# 8266_DIYIOT_Board_H_G_B_R_GND.net
KiCad netlist of a schematic drawn in EAGLE
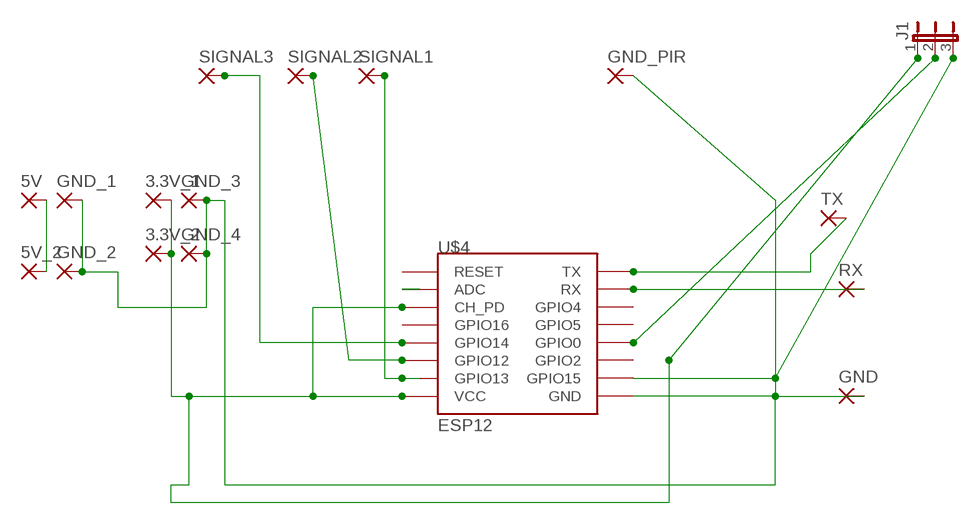
[diagram p0: schematic, sheet 1]

(export (version "E")
  (design (tool "Eeschema 10.0.6"))
  (components
    (comp (ref "3.3V_1")
      (value "2,15/1,0")
      (footprint "eagle-import:2,15_1,0")
      (libsource (lib "eagle-import") (part "2,15/1,0"))
    )
    (comp (ref "3.3V_2")
      (value "2,15/1,0")
      (footprint "eagle-import:2,15_1,0")
      (libsource (lib "eagle-import") (part "2,15/1,0"))
    )
    (comp (ref "5V")
      (value "2,15/1,0")
      (footprint "eagle-import:2,15_1,0")
      (libsource (lib "eagle-import") (part "2,15/1,0"))
    )
    (comp (ref "5V_2")
      (value "2,15/1,0")
      (footprint "eagle-import:2,15_1,0")
      (libsource (lib "eagle-import") (part "2,15/1,0"))
    )
    (comp (ref "GND")
      (value "2,15/1,0")
      (footprint "eagle-import:2,15_1,0")
      (libsource (lib "eagle-import") (part "2,15/1,0"))
    )
    (comp (ref "GND_1")
      (value "2,15/1,0")
      (footprint "eagle-import:2,15_1,0")
      (libsource (lib "eagle-import") (part "2,15/1,0"))
    )
    (comp (ref "GND_2")
      (value "2,15/1,0")
      (footprint "eagle-import:2,15_1,0")
      (libsource (lib "eagle-import") (part "2,15/1,0"))
    )
    (comp (ref "GND_3")
      (value "2,15/1,0")
      (footprint "eagle-import:2,15_1,0")
      (libsource (lib "eagle-import") (part "2,15/1,0"))
    )
    (comp (ref "GND_4")
      (value "2,15/1,0")
      (footprint "eagle-import:2,15_1,0")
      (libsource (lib "eagle-import") (part "2,15/1,0"))
    )
    (comp (ref "GND_PIR")
      (value "2,15/1,0")
      (footprint "eagle-import:2,15_1,0")
      (libsource (lib "eagle-import") (part "2,15/1,0"))
    )
    (comp (ref "J1")
      (value "JP2E")
      (footprint "eagle-import:JP2")
      (libsource (lib "eagle-import") (part "JP2E"))
    )
    (comp (ref "RX")
      (value "2,15/1,0")
      (footprint "eagle-import:2,15_1,0")
      (libsource (lib "eagle-import") (part "2,15/1,0"))
    )
    (comp (ref "SIGNAL1")
      (value "2,15/1,0")
      (footprint "eagle-import:2,15_1,0")
      (libsource (lib "eagle-import") (part "2,15/1,0"))
    )
    (comp (ref "SIGNAL2")
      (value "2,15/1,0")
      (footprint "eagle-import:2,15_1,0")
      (libsource (lib "eagle-import") (part "2,15/1,0"))
    )
    (comp (ref "SIGNAL3")
      (value "2,15/1,0")
      (footprint "eagle-import:2,15_1,0")
      (libsource (lib "eagle-import") (part "2,15/1,0"))
    )
    (comp (ref "TX")
      (value "2,15/1,0")
      (footprint "eagle-import:2,15_1,0")
      (libsource (lib "eagle-import") (part "2,15/1,0"))
    )
    (comp (ref "U$4")
      (value "ESP12")
      (footprint "eagle-import:ESP12")
      (libsource (lib "eagle-import") (part "ESP12"))
    )
  )
  (nets
    (net (code "1") (name "/5V") (class "Default")
      (node (ref "5V") (pin "1") (pinfunction "P_1") (pintype "passive"))
      (node (ref "5V_2") (pin "1") (pinfunction "P_1") (pintype "passive"))
      (node (ref "GND") (pin "1") (pinfunction "P_1") (pintype "passive"))
      (node (ref "GND_1") (pin "1") (pinfunction "P_1") (pintype "passive"))
      (node (ref "GND_2") (pin "1") (pinfunction "P_1") (pintype "passive"))
      (node (ref "GND_3") (pin "1") (pinfunction "P_1") (pintype "passive"))
      (node (ref "GND_4") (pin "1") (pinfunction "P_1") (pintype "passive"))
      (node (ref "GND_PIR") (pin "1") (pinfunction "P_1") (pintype "passive"))
      (node (ref "J1") (pin "3") (pinfunction "3_3") (pintype "passive"))
      (node (ref "U$4") (pin "GND") (pinfunction "GND_GND") (pintype "bidirectional"))
      (node (ref "U$4") (pin "GPIO15") (pinfunction "GPIO15_GPIO15") (pintype "bidirectional"))
    )
    (net (code "2") (name "Net-(3.3V_1-P)") (class "Default")
      (node (ref "3.3V_1") (pin "1") (pinfunction "P_1") (pintype "passive"))
      (node (ref "3.3V_2") (pin "1") (pinfunction "P_1") (pintype "passive"))
      (node (ref "J1") (pin "1") (pinfunction "1_1") (pintype "passive"))
      (node (ref "U$4") (pin "CH_PD") (pinfunction "CH_PD_CH_PD") (pintype "bidirectional"))
      (node (ref "U$4") (pin "VCC") (pinfunction "VCC_VCC") (pintype "bidirectional"))
    )
    (net (code "3") (name "Net-(J1-Pad2)") (class "Default")
      (node (ref "J1") (pin "2") (pinfunction "2_2") (pintype "passive"))
      (node (ref "U$4") (pin "GPIO0") (pinfunction "GPIO0_GPIO0") (pintype "bidirectional"))
    )
    (net (code "4") (name "Net-(RX-P)") (class "Default")
      (node (ref "RX") (pin "1") (pinfunction "P_1") (pintype "passive"))
      (node (ref "U$4") (pin "RX") (pinfunction "RX_RX") (pintype "bidirectional"))
    )
    (net (code "5") (name "Net-(SIGNAL1-P)") (class "Default")
      (node (ref "SIGNAL1") (pin "1") (pinfunction "P_1") (pintype "passive"))
      (node (ref "U$4") (pin "GPIO13") (pinfunction "GPIO13_GPIO13") (pintype "bidirectional"))
    )
    (net (code "6") (name "Net-(SIGNAL2-P)") (class "Default")
      (node (ref "SIGNAL2") (pin "1") (pinfunction "P_1") (pintype "passive"))
      (node (ref "U$4") (pin "GPIO12") (pinfunction "GPIO12_GPIO12") (pintype "bidirectional"))
    )
    (net (code "7") (name "Net-(SIGNAL3-P)") (class "Default")
      (node (ref "SIGNAL3") (pin "1") (pinfunction "P_1") (pintype "passive"))
      (node (ref "U$4") (pin "GPIO14") (pinfunction "GPIO14_GPIO14") (pintype "bidirectional"))
    )
    (net (code "8") (name "Net-(TX-P)") (class "Default")
      (node (ref "TX") (pin "1") (pinfunction "P_1") (pintype "passive"))
      (node (ref "U$4") (pin "TX") (pinfunction "TX_TX") (pintype "bidirectional"))
    )
    (net (code "9") (name "unconnected-(U$4-PadADC)") (class "Default")
      (node (ref "U$4") (pin "ADC") (pinfunction "ADC_ADC") (pintype "bidirectional"))
    )
    (net (code "10") (name "unconnected-(U$4-PadGPIO2)") (class "Default")
      (node (ref "U$4") (pin "GPIO2") (pinfunction "GPIO2_GPIO2") (pintype "bidirectional"))
    )
    (net (code "11") (name "unconnected-(U$4-PadGPIO4)") (class "Default")
      (node (ref "U$4") (pin "GPIO4") (pinfunction "GPIO4_GPIO4") (pintype "bidirectional"))
    )
    (net (code "12") (name "unconnected-(U$4-PadGPIO5)") (class "Default")
      (node (ref "U$4") (pin "GPIO5") (pinfunction "GPIO5_GPIO5") (pintype "bidirectional"))
    )
    (net (code "13") (name "unconnected-(U$4-PadGPIO16)") (class "Default")
      (node (ref "U$4") (pin "GPIO16") (pinfunction "GPIO16_GPIO16") (pintype "bidirectional"))
    )
    (net (code "14") (name "unconnected-(U$4-PadRESET)") (class "Default")
      (node (ref "U$4") (pin "RESET") (pinfunction "RESET_RESET") (pintype "bidirectional"))
    )
  )
)
